# FPGABank1X.net
KiCad netlist of a schematic drawn in Altium Designer
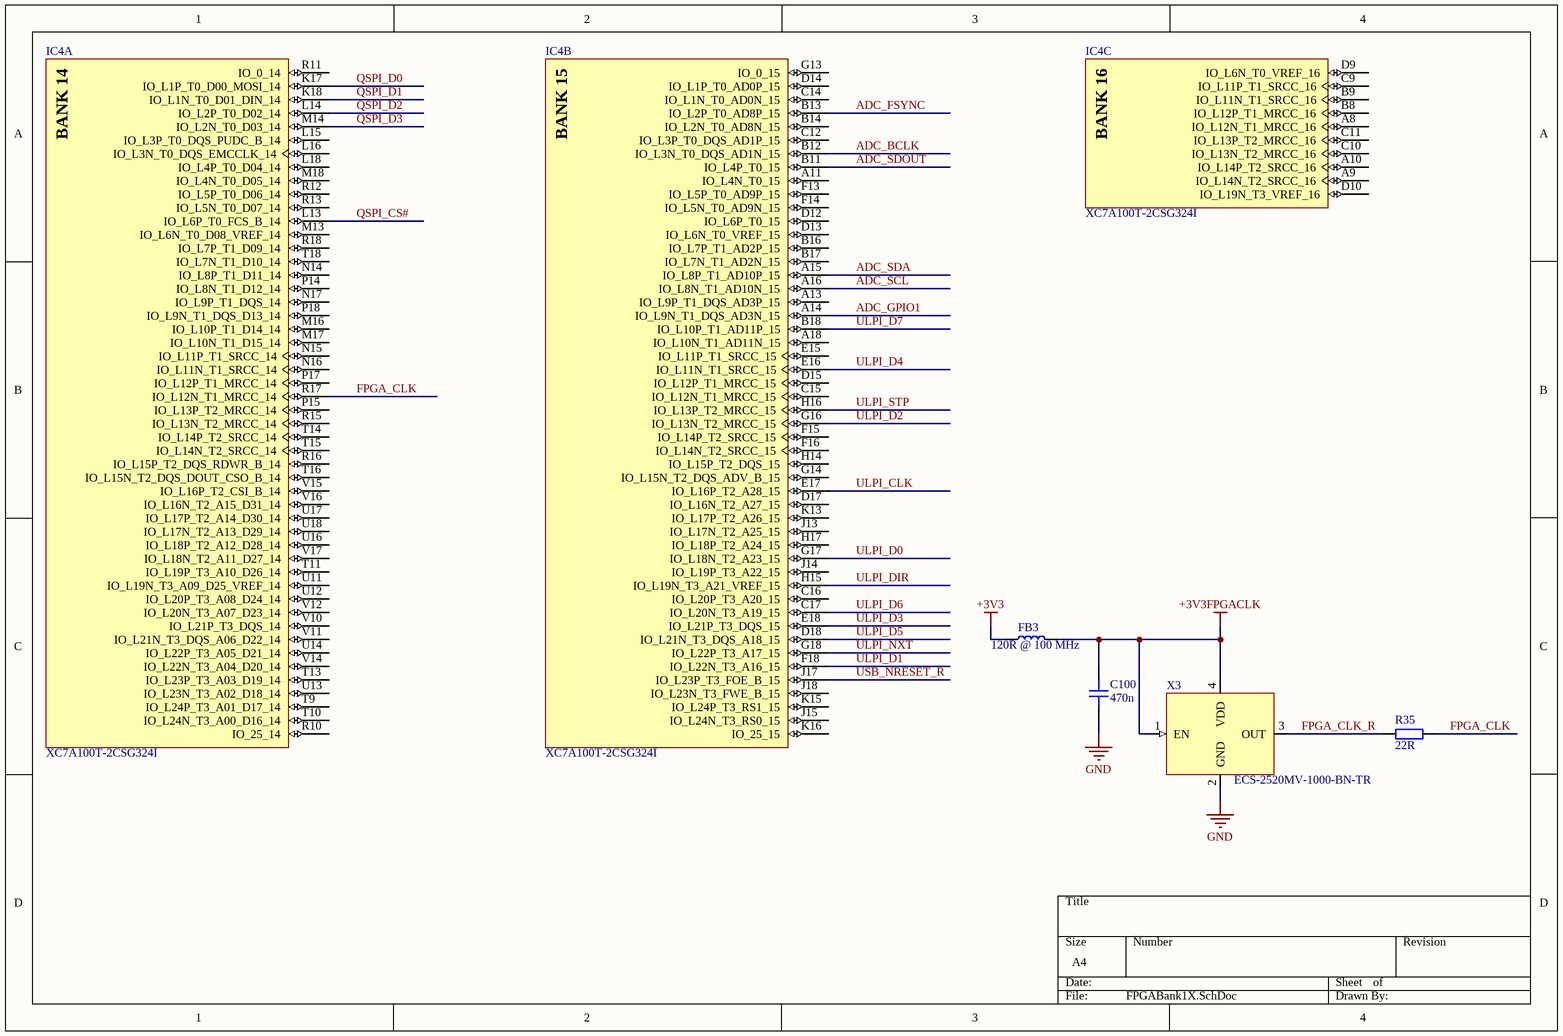
[diagram p0: FPGABank1X.SchDoc]

(export (version "E")
  (design (tool "Eeschema 10.0.6"))
  (components
    (comp (ref "C100")
      (value "470n")
      (footprint "CAP_0201")
      (description "Capacitor SMD 0201")
      (libsource (lib "Schematic-Lib-PhilsLab") (part "CAP_0201"))
    )
    (comp (ref "FB3")
      (value "120R @ 100 MHz")
      (footprint "Footprint-Lib-PhilsLab:IND_0201")
      (description "Inductor SMD 0201")
      (fields
        (field (name "MANUFACTURER_PART_NUMBER") "LQP03HQ56NH02D")
        (field (name "MOUSER PART NUMBER") "81-LQP03HQ56NH02D")
      )
      (libsource (lib "Schematic-Lib-PhilsLab") (part "IND_0201"))
    )
    (comp (ref "IC4")
      (value "XC7A100T-2CSG324I")
      (footprint "CSG324")
      (description "Artix-7 FPGA, 210 User I/Os, 0 GTP, 324-Ball BGA, Speed Grade 2, Industrial Grade, Pb-Free")
      (fields (field (name "GENERIC PART NUMBER") "XC7A100T") (field (name "MANUFACTURER") "Xilinx"))
      (libsource (lib "Schematic-Lib-PhilsLab") (part "XC7A100T-2CSG324I"))
    )
    (comp (ref "R35")
      (value "22R")
      (footprint "RES_0201")
      (description "Resistor SMD 0201")
      (libsource (lib "Schematic-Lib-PhilsLab") (part "RES_0201"))
    )
    (comp (ref "X3")
      (value "ECS-2520MV-1000-BN-TR")
      (footprint "XTAL_2520")
      (fields
        (field (name "MANUFACTURER") "ECS")
        (field (name "MANUFACTURER PART NUMBER") "ECS-2520MV-130-BN-TR")
      )
      (libsource (lib "Schematic-Lib-PhilsLab") (part "ECS-2520MV-130-BN-TR"))
    )
  )
  (nets
    (net (code "1") (name "+3V3") (class "Default")
      (node (ref "FB3") (pin "1") (pinfunction "1_1") (pintype "passive"))
    )
    (net (code "2") (name "+3V3FPGACLK") (class "Default")
      (node (ref "C100") (pin "2") (pinfunction "2_2") (pintype "passive"))
      (node (ref "FB3") (pin "2") (pinfunction "2_2") (pintype "passive"))
      (node (ref "X3") (pin "1") (pinfunction "EN_1") (pintype "input"))
      (node (ref "X3") (pin "4") (pinfunction "VDD_4") (pintype "power_in"))
    )
    (net (code "3") (name "/ADC_BCLK") (class "Default")
      (node (ref "IC4") (pin "B12") (pinfunction "IO_L3N_T0_DQS_AD1N_15_B12") (pintype "bidirectional"))
    )
    (net (code "4") (name "/ADC_FSYNC") (class "Default")
      (node (ref "IC4") (pin "B13") (pinfunction "IO_L2P_T0_AD8P_15_B13") (pintype "bidirectional"))
    )
    (net (code "5") (name "/ADC_GPIO1") (class "Default")
      (node (ref "IC4") (pin "A14") (pinfunction "IO_L9N_T1_DQS_AD3N_15_A14") (pintype "bidirectional"))
    )
    (net (code "6") (name "/ADC_SCL") (class "Default")
      (node (ref "IC4") (pin "A16") (pinfunction "IO_L8N_T1_AD10N_15_A16") (pintype "bidirectional"))
    )
    (net (code "7") (name "/ADC_SDA") (class "Default")
      (node (ref "IC4") (pin "A15") (pinfunction "IO_L8P_T1_AD10P_15_A15") (pintype "bidirectional"))
    )
    (net (code "8") (name "/ADC_SDOUT") (class "Default")
      (node (ref "IC4") (pin "B11") (pinfunction "IO_L4P_T0_15_B11") (pintype "bidirectional"))
    )
    (net (code "9") (name "/FPGA_CLK") (class "Default")
      (node (ref "IC4") (pin "R17") (pinfunction "IO_L12N_T1_MRCC_14_R17") (pintype "bidirectional"))
      (node (ref "R35") (pin "2") (pinfunction "2_2") (pintype "passive"))
    )
    (net (code "10") (name "/FPGA_CLK_R") (class "Default")
      (node (ref "R35") (pin "1") (pinfunction "1_1") (pintype "passive"))
      (node (ref "X3") (pin "3") (pinfunction "OUT_3") (pintype "passive"))
    )
    (net (code "11") (name "/QSPI_CS#") (class "Default")
      (node (ref "IC4") (pin "L13") (pinfunction "IO_L6P_T0_FCS_B_14_L13") (pintype "bidirectional"))
    )
    (net (code "12") (name "/QSPI_D0") (class "Default")
      (node (ref "IC4") (pin "K17") (pinfunction "IO_L1P_T0_D00_MOSI_14_K17") (pintype "bidirectional"))
    )
    (net (code "13") (name "/QSPI_D1") (class "Default")
      (node (ref "IC4") (pin "K18") (pinfunction "IO_L1N_T0_D01_DIN_14_K18") (pintype "bidirectional"))
    )
    (net (code "14") (name "/QSPI_D2") (class "Default")
      (node (ref "IC4") (pin "L14") (pinfunction "IO_L2P_T0_D02_14_L14") (pintype "bidirectional"))
    )
    (net (code "15") (name "/QSPI_D3") (class "Default")
      (node (ref "IC4") (pin "M14") (pinfunction "IO_L2N_T0_D03_14_M14") (pintype "bidirectional"))
    )
    (net (code "16") (name "/ULPI_CLK") (class "Default")
      (node (ref "IC4") (pin "E17") (pinfunction "IO_L16P_T2_A28_15_E17") (pintype "bidirectional"))
    )
    (net (code "17") (name "/ULPI_D0") (class "Default")
      (node (ref "IC4") (pin "G17") (pinfunction "IO_L18N_T2_A23_15_G17") (pintype "bidirectional"))
    )
    (net (code "18") (name "/ULPI_D1") (class "Default")
      (node (ref "IC4") (pin "F18") (pinfunction "IO_L22N_T3_A16_15_F18") (pintype "bidirectional"))
    )
    (net (code "19") (name "/ULPI_D2") (class "Default")
      (node (ref "IC4") (pin "G16") (pinfunction "IO_L13N_T2_MRCC_15_G16") (pintype "bidirectional"))
    )
    (net (code "20") (name "/ULPI_D3") (class "Default")
      (node (ref "IC4") (pin "E18") (pinfunction "IO_L21P_T3_DQS_15_E18") (pintype "bidirectional"))
    )
    (net (code "21") (name "/ULPI_D4") (class "Default")
      (node (ref "IC4") (pin "E16") (pinfunction "IO_L11N_T1_SRCC_15_E16") (pintype "bidirectional"))
    )
    (net (code "22") (name "/ULPI_D5") (class "Default")
      (node (ref "IC4") (pin "D18") (pinfunction "IO_L21N_T3_DQS_A18_15_D18") (pintype "bidirectional"))
    )
    (net (code "23") (name "/ULPI_D6") (class "Default")
      (node (ref "IC4") (pin "C17") (pinfunction "IO_L20N_T3_A19_15_C17") (pintype "bidirectional"))
    )
    (net (code "24") (name "/ULPI_D7") (class "Default")
      (node (ref "IC4") (pin "B18") (pinfunction "IO_L10P_T1_AD11P_15_B18") (pintype "bidirectional"))
    )
    (net (code "25") (name "/ULPI_DIR") (class "Default")
      (node (ref "IC4") (pin "H15") (pinfunction "IO_L19N_T3_A21_VREF_15_H15") (pintype "bidirectional"))
    )
    (net (code "26") (name "/ULPI_NXT") (class "Default")
      (node (ref "IC4") (pin "G18") (pinfunction "IO_L22P_T3_A17_15_G18") (pintype "bidirectional"))
    )
    (net (code "27") (name "/ULPI_STP") (class "Default")
      (node (ref "IC4") (pin "H16") (pinfunction "IO_L13P_T2_MRCC_15_H16") (pintype "bidirectional"))
    )
    (net (code "28") (name "/USB_NRESET_R") (class "Default")
      (node (ref "IC4") (pin "J17") (pinfunction "IO_L23P_T3_FOE_B_15_J17") (pintype "bidirectional"))
    )
    (net (code "29") (name "GND") (class "Default")
      (node (ref "C100") (pin "1") (pinfunction "1_1") (pintype "passive"))
      (node (ref "X3") (pin "2") (pinfunction "GND_2") (pintype "power_in"))
    )
    (net (code "30") (name "unconnected-(IC4A-IO_0_14-PadR11)") (class "Default")
      (node (ref "IC4") (pin "R11") (pinfunction "IO_0_14_R11") (pintype "bidirectional"))
    )
    (net (code "31") (name "unconnected-(IC4A-IO_25_14-PadR10)") (class "Default")
      (node (ref "IC4") (pin "R10") (pinfunction "IO_25_14_R10") (pintype "bidirectional"))
    )
    (net (code "32") (name "unconnected-(IC4A-IO_L3N_T0_DQS_EMCCLK_14-PadL16)") (class "Default")
      (node (ref "IC4") (pin "L16") (pinfunction "IO_L3N_T0_DQS_EMCCLK_14_L16") (pintype "bidirectional"))
    )
    (net (code "33") (name "unconnected-(IC4A-IO_L3P_T0_DQS_PUDC_B_14-PadL15)") (class "Default")
      (node (ref "IC4") (pin "L15") (pinfunction "IO_L3P_T0_DQS_PUDC_B_14_L15") (pintype "bidirectional"))
    )
    (net (code "34") (name "unconnected-(IC4A-IO_L4N_T0_D05_14-PadM18)") (class "Default")
      (node (ref "IC4") (pin "M18") (pinfunction "IO_L4N_T0_D05_14_M18") (pintype "bidirectional"))
    )
    (net (code "35") (name "unconnected-(IC4A-IO_L4P_T0_D04_14-PadL18)") (class "Default")
      (node (ref "IC4") (pin "L18") (pinfunction "IO_L4P_T0_D04_14_L18") (pintype "bidirectional"))
    )
    (net (code "36") (name "unconnected-(IC4A-IO_L5N_T0_D07_14-PadR13)") (class "Default")
      (node (ref "IC4") (pin "R13") (pinfunction "IO_L5N_T0_D07_14_R13") (pintype "bidirectional"))
    )
    (net (code "37") (name "unconnected-(IC4A-IO_L5P_T0_D06_14-PadR12)") (class "Default")
      (node (ref "IC4") (pin "R12") (pinfunction "IO_L5P_T0_D06_14_R12") (pintype "bidirectional"))
    )
    (net (code "38") (name "unconnected-(IC4A-IO_L6N_T0_D08_VREF_14-PadM13)") (class "Default")
      (node (ref "IC4") (pin "M13") (pinfunction "IO_L6N_T0_D08_VREF_14_M13") (pintype "bidirectional"))
    )
    (net (code "39") (name "unconnected-(IC4A-IO_L7N_T1_D10_14-PadT18)") (class "Default")
      (node (ref "IC4") (pin "T18") (pinfunction "IO_L7N_T1_D10_14_T18") (pintype "bidirectional"))
    )
    (net (code "40") (name "unconnected-(IC4A-IO_L7P_T1_D09_14-PadR18)") (class "Default")
      (node (ref "IC4") (pin "R18") (pinfunction "IO_L7P_T1_D09_14_R18") (pintype "bidirectional"))
    )
    (net (code "41") (name "unconnected-(IC4A-IO_L8N_T1_D12_14-PadP14)") (class "Default")
      (node (ref "IC4") (pin "P14") (pinfunction "IO_L8N_T1_D12_14_P14") (pintype "bidirectional"))
    )
    (net (code "42") (name "unconnected-(IC4A-IO_L8P_T1_D11_14-PadN14)") (class "Default")
      (node (ref "IC4") (pin "N14") (pinfunction "IO_L8P_T1_D11_14_N14") (pintype "bidirectional"))
    )
    (net (code "43") (name "unconnected-(IC4A-IO_L9N_T1_DQS_D13_14-PadP18)") (class "Default")
      (node (ref "IC4") (pin "P18") (pinfunction "IO_L9N_T1_DQS_D13_14_P18") (pintype "bidirectional"))
    )
    (net (code "44") (name "unconnected-(IC4A-IO_L9P_T1_DQS_14-PadN17)") (class "Default")
      (node (ref "IC4") (pin "N17") (pinfunction "IO_L9P_T1_DQS_14_N17") (pintype "bidirectional"))
    )
    (net (code "45") (name "unconnected-(IC4A-IO_L10N_T1_D15_14-PadM17)") (class "Default")
      (node (ref "IC4") (pin "M17") (pinfunction "IO_L10N_T1_D15_14_M17") (pintype "bidirectional"))
    )
    (net (code "46") (name "unconnected-(IC4A-IO_L10P_T1_D14_14-PadM16)") (class "Default")
      (node (ref "IC4") (pin "M16") (pinfunction "IO_L10P_T1_D14_14_M16") (pintype "bidirectional"))
    )
    (net (code "47") (name "unconnected-(IC4A-IO_L11N_T1_SRCC_14-PadN16)") (class "Default")
      (node (ref "IC4") (pin "N16") (pinfunction "IO_L11N_T1_SRCC_14_N16") (pintype "bidirectional"))
    )
    (net (code "48") (name "unconnected-(IC4A-IO_L11P_T1_SRCC_14-PadN15)") (class "Default")
      (node (ref "IC4") (pin "N15") (pinfunction "IO_L11P_T1_SRCC_14_N15") (pintype "bidirectional"))
    )
    (net (code "49") (name "unconnected-(IC4A-IO_L12P_T1_MRCC_14-PadP17)") (class "Default")
      (node (ref "IC4") (pin "P17") (pinfunction "IO_L12P_T1_MRCC_14_P17") (pintype "bidirectional"))
    )
    (net (code "50") (name "unconnected-(IC4A-IO_L13N_T2_MRCC_14-PadR15)") (class "Default")
      (node (ref "IC4") (pin "R15") (pinfunction "IO_L13N_T2_MRCC_14_R15") (pintype "bidirectional"))
    )
    (net (code "51") (name "unconnected-(IC4A-IO_L13P_T2_MRCC_14-PadP15)") (class "Default")
      (node (ref "IC4") (pin "P15") (pinfunction "IO_L13P_T2_MRCC_14_P15") (pintype "bidirectional"))
    )
    (net (code "52") (name "unconnected-(IC4A-IO_L14N_T2_SRCC_14-PadT15)") (class "Default")
      (node (ref "IC4") (pin "T15") (pinfunction "IO_L14N_T2_SRCC_14_T15") (pintype "bidirectional"))
    )
    (net (code "53") (name "unconnected-(IC4A-IO_L14P_T2_SRCC_14-PadT14)") (class "Default")
      (node (ref "IC4") (pin "T14") (pinfunction "IO_L14P_T2_SRCC_14_T14") (pintype "bidirectional"))
    )
    (net (code "54") (name "unconnected-(IC4A-IO_L15N_T2_DQS_DOUT_CSO_B_14-PadT16)") (class "Default")
      (node (ref "IC4") (pin "T16") (pinfunction "IO_L15N_T2_DQS_DOUT_CSO_B_14_T16") (pintype "bidirectional"))
    )
    (net (code "55") (name "unconnected-(IC4A-IO_L15P_T2_DQS_RDWR_B_14-PadR16)") (class "Default")
      (node (ref "IC4") (pin "R16") (pinfunction "IO_L15P_T2_DQS_RDWR_B_14_R16") (pintype "bidirectional"))
    )
    (net (code "56") (name "unconnected-(IC4A-IO_L16N_T2_A15_D31_14-PadV16)") (class "Default")
      (node (ref "IC4") (pin "V16") (pinfunction "IO_L16N_T2_A15_D31_14_V16") (pintype "bidirectional"))
    )
    (net (code "57") (name "unconnected-(IC4A-IO_L16P_T2_CSI_B_14-PadV15)") (class "Default")
      (node (ref "IC4") (pin "V15") (pinfunction "IO_L16P_T2_CSI_B_14_V15") (pintype "bidirectional"))
    )
    (net (code "58") (name "unconnected-(IC4A-IO_L17N_T2_A13_D29_14-PadU18)") (class "Default")
      (node (ref "IC4") (pin "U18") (pinfunction "IO_L17N_T2_A13_D29_14_U18") (pintype "bidirectional"))
    )
    (net (code "59") (name "unconnected-(IC4A-IO_L17P_T2_A14_D30_14-PadU17)") (class "Default")
      (node (ref "IC4") (pin "U17") (pinfunction "IO_L17P_T2_A14_D30_14_U17") (pintype "bidirectional"))
    )
    (net (code "60") (name "unconnected-(IC4A-IO_L18N_T2_A11_D27_14-PadV17)") (class "Default")
      (node (ref "IC4") (pin "V17") (pinfunction "IO_L18N_T2_A11_D27_14_V17") (pintype "bidirectional"))
    )
    (net (code "61") (name "unconnected-(IC4A-IO_L18P_T2_A12_D28_14-PadU16)") (class "Default")
      (node (ref "IC4") (pin "U16") (pinfunction "IO_L18P_T2_A12_D28_14_U16") (pintype "bidirectional"))
    )
    (net (code "62") (name "unconnected-(IC4A-IO_L19N_T3_A09_D25_VREF_14-PadU11)") (class "Default")
      (node (ref "IC4") (pin "U11") (pinfunction "IO_L19N_T3_A09_D25_VREF_14_U11") (pintype "bidirectional"))
    )
    (net (code "63") (name "unconnected-(IC4A-IO_L19P_T3_A10_D26_14-PadT11)") (class "Default")
      (node (ref "IC4") (pin "T11") (pinfunction "IO_L19P_T3_A10_D26_14_T11") (pintype "bidirectional"))
    )
    (net (code "64") (name "unconnected-(IC4A-IO_L20N_T3_A07_D23_14-PadV12)") (class "Default")
      (node (ref "IC4") (pin "V12") (pinfunction "IO_L20N_T3_A07_D23_14_V12") (pintype "bidirectional"))
    )
    (net (code "65") (name "unconnected-(IC4A-IO_L20P_T3_A08_D24_14-PadU12)") (class "Default")
      (node (ref "IC4") (pin "U12") (pinfunction "IO_L20P_T3_A08_D24_14_U12") (pintype "bidirectional"))
    )
    (net (code "66") (name "unconnected-(IC4A-IO_L21N_T3_DQS_A06_D22_14-PadV11)") (class "Default")
      (node (ref "IC4") (pin "V11") (pinfunction "IO_L21N_T3_DQS_A06_D22_14_V11") (pintype "bidirectional"))
    )
    (net (code "67") (name "unconnected-(IC4A-IO_L21P_T3_DQS_14-PadV10)") (class "Default")
      (node (ref "IC4") (pin "V10") (pinfunction "IO_L21P_T3_DQS_14_V10") (pintype "bidirectional"))
    )
    (net (code "68") (name "unconnected-(IC4A-IO_L22N_T3_A04_D20_14-PadV14)") (class "Default")
      (node (ref "IC4") (pin "V14") (pinfunction "IO_L22N_T3_A04_D20_14_V14") (pintype "bidirectional"))
    )
    (net (code "69") (name "unconnected-(IC4A-IO_L22P_T3_A05_D21_14-PadU14)") (class "Default")
      (node (ref "IC4") (pin "U14") (pinfunction "IO_L22P_T3_A05_D21_14_U14") (pintype "bidirectional"))
    )
    (net (code "70") (name "unconnected-(IC4A-IO_L23N_T3_A02_D18_14-PadU13)") (class "Default")
      (node (ref "IC4") (pin "U13") (pinfunction "IO_L23N_T3_A02_D18_14_U13") (pintype "bidirectional"))
    )
    (net (code "71") (name "unconnected-(IC4A-IO_L23P_T3_A03_D19_14-PadT13)") (class "Default")
      (node (ref "IC4") (pin "T13") (pinfunction "IO_L23P_T3_A03_D19_14_T13") (pintype "bidirectional"))
    )
    (net (code "72") (name "unconnected-(IC4A-IO_L24N_T3_A00_D16_14-PadT10)") (class "Default")
      (node (ref "IC4") (pin "T10") (pinfunction "IO_L24N_T3_A00_D16_14_T10") (pintype "bidirectional"))
    )
    (net (code "73") (name "unconnected-(IC4A-IO_L24P_T3_A01_D17_14-PadT9)") (class "Default")
      (node (ref "IC4") (pin "T9") (pinfunction "IO_L24P_T3_A01_D17_14_T9") (pintype "bidirectional"))
    )
    (net (code "74") (name "unconnected-(IC4B-IO_0_15-PadG13)") (class "Default")
      (node (ref "IC4") (pin "G13") (pinfunction "IO_0_15_G13") (pintype "bidirectional"))
    )
    (net (code "75") (name "unconnected-(IC4B-IO_25_15-PadK16)") (class "Default")
      (node (ref "IC4") (pin "K16") (pinfunction "IO_25_15_K16") (pintype "bidirectional"))
    )
    (net (code "76") (name "unconnected-(IC4B-IO_L1N_T0_AD0N_15-PadC14)") (class "Default")
      (node (ref "IC4") (pin "C14") (pinfunction "IO_L1N_T0_AD0N_15_C14") (pintype "bidirectional"))
    )
    (net (code "77") (name "unconnected-(IC4B-IO_L1P_T0_AD0P_15-PadD14)") (class "Default")
      (node (ref "IC4") (pin "D14") (pinfunction "IO_L1P_T0_AD0P_15_D14") (pintype "bidirectional"))
    )
    (net (code "78") (name "unconnected-(IC4B-IO_L2N_T0_AD8N_15-PadB14)") (class "Default")
      (node (ref "IC4") (pin "B14") (pinfunction "IO_L2N_T0_AD8N_15_B14") (pintype "bidirectional"))
    )
    (net (code "79") (name "unconnected-(IC4B-IO_L3P_T0_DQS_AD1P_15-PadC12)") (class "Default")
      (node (ref "IC4") (pin "C12") (pinfunction "IO_L3P_T0_DQS_AD1P_15_C12") (pintype "bidirectional"))
    )
    (net (code "80") (name "unconnected-(IC4B-IO_L4N_T0_15-PadA11)") (class "Default")
      (node (ref "IC4") (pin "A11") (pinfunction "IO_L4N_T0_15_A11") (pintype "bidirectional"))
    )
    (net (code "81") (name "unconnected-(IC4B-IO_L5N_T0_AD9N_15-PadF14)") (class "Default")
      (node (ref "IC4") (pin "F14") (pinfunction "IO_L5N_T0_AD9N_15_F14") (pintype "bidirectional"))
    )
    (net (code "82") (name "unconnected-(IC4B-IO_L5P_T0_AD9P_15-PadF13)") (class "Default")
      (node (ref "IC4") (pin "F13") (pinfunction "IO_L5P_T0_AD9P_15_F13") (pintype "bidirectional"))
    )
    (net (code "83") (name "unconnected-(IC4B-IO_L6N_T0_VREF_15-PadD13)") (class "Default")
      (node (ref "IC4") (pin "D13") (pinfunction "IO_L6N_T0_VREF_15_D13") (pintype "bidirectional"))
    )
    (net (code "84") (name "unconnected-(IC4B-IO_L6P_T0_15-PadD12)") (class "Default")
      (node (ref "IC4") (pin "D12") (pinfunction "IO_L6P_T0_15_D12") (pintype "bidirectional"))
    )
    (net (code "85") (name "unconnected-(IC4B-IO_L7N_T1_AD2N_15-PadB17)") (class "Default")
      (node (ref "IC4") (pin "B17") (pinfunction "IO_L7N_T1_AD2N_15_B17") (pintype "bidirectional"))
    )
    (net (code "86") (name "unconnected-(IC4B-IO_L7P_T1_AD2P_15-PadB16)") (class "Default")
      (node (ref "IC4") (pin "B16") (pinfunction "IO_L7P_T1_AD2P_15_B16") (pintype "bidirectional"))
    )
    (net (code "87") (name "unconnected-(IC4B-IO_L9P_T1_DQS_AD3P_15-PadA13)") (class "Default")
      (node (ref "IC4") (pin "A13") (pinfunction "IO_L9P_T1_DQS_AD3P_15_A13") (pintype "bidirectional"))
    )
    (net (code "88") (name "unconnected-(IC4B-IO_L10N_T1_AD11N_15-PadA18)") (class "Default")
      (node (ref "IC4") (pin "A18") (pinfunction "IO_L10N_T1_AD11N_15_A18") (pintype "bidirectional"))
    )
    (net (code "89") (name "unconnected-(IC4B-IO_L11P_T1_SRCC_15-PadE15)") (class "Default")
      (node (ref "IC4") (pin "E15") (pinfunction "IO_L11P_T1_SRCC_15_E15") (pintype "bidirectional"))
    )
    (net (code "90") (name "unconnected-(IC4B-IO_L12N_T1_MRCC_15-PadC15)") (class "Default")
      (node (ref "IC4") (pin "C15") (pinfunction "IO_L12N_T1_MRCC_15_C15") (pintype "bidirectional"))
    )
    (net (code "91") (name "unconnected-(IC4B-IO_L12P_T1_MRCC_15-PadD15)") (class "Default")
      (node (ref "IC4") (pin "D15") (pinfunction "IO_L12P_T1_MRCC_15_D15") (pintype "bidirectional"))
    )
    (net (code "92") (name "unconnected-(IC4B-IO_L14N_T2_SRCC_15-PadF16)") (class "Default")
      (node (ref "IC4") (pin "F16") (pinfunction "IO_L14N_T2_SRCC_15_F16") (pintype "bidirectional"))
    )
    (net (code "93") (name "unconnected-(IC4B-IO_L14P_T2_SRCC_15-PadF15)") (class "Default")
      (node (ref "IC4") (pin "F15") (pinfunction "IO_L14P_T2_SRCC_15_F15") (pintype "bidirectional"))
    )
    (net (code "94") (name "unconnected-(IC4B-IO_L15N_T2_DQS_ADV_B_15-PadG14)") (class "Default")
      (node (ref "IC4") (pin "G14") (pinfunction "IO_L15N_T2_DQS_ADV_B_15_G14") (pintype "bidirectional"))
    )
    (net (code "95") (name "unconnected-(IC4B-IO_L15P_T2_DQS_15-PadH14)") (class "Default")
      (node (ref "IC4") (pin "H14") (pinfunction "IO_L15P_T2_DQS_15_H14") (pintype "bidirectional"))
    )
    (net (code "96") (name "unconnected-(IC4B-IO_L16N_T2_A27_15-PadD17)") (class "Default")
      (node (ref "IC4") (pin "D17") (pinfunction "IO_L16N_T2_A27_15_D17") (pintype "bidirectional"))
    )
    (net (code "97") (name "unconnected-(IC4B-IO_L17N_T2_A25_15-PadJ13)") (class "Default")
      (node (ref "IC4") (pin "J13") (pinfunction "IO_L17N_T2_A25_15_J13") (pintype "bidirectional"))
    )
    (net (code "98") (name "unconnected-(IC4B-IO_L17P_T2_A26_15-PadK13)") (class "Default")
      (node (ref "IC4") (pin "K13") (pinfunction "IO_L17P_T2_A26_15_K13") (pintype "bidirectional"))
    )
    (net (code "99") (name "unconnected-(IC4B-IO_L18P_T2_A24_15-PadH17)") (class "Default")
      (node (ref "IC4") (pin "H17") (pinfunction "IO_L18P_T2_A24_15_H17") (pintype "bidirectional"))
    )
    (net (code "100") (name "unconnected-(IC4B-IO_L19P_T3_A22_15-PadJ14)") (class "Default")
      (node (ref "IC4") (pin "J14") (pinfunction "IO_L19P_T3_A22_15_J14") (pintype "bidirectional"))
    )
    (net (code "101") (name "unconnected-(IC4B-IO_L20P_T3_A20_15-PadC16)") (class "Default")
      (node (ref "IC4") (pin "C16") (pinfunction "IO_L20P_T3_A20_15_C16") (pintype "bidirectional"))
    )
    (net (code "102") (name "unconnected-(IC4B-IO_L23N_T3_FWE_B_15-PadJ18)") (class "Default")
      (node (ref "IC4") (pin "J18") (pinfunction "IO_L23N_T3_FWE_B_15_J18") (pintype "bidirectional"))
    )
    (net (code "103") (name "unconnected-(IC4B-IO_L24N_T3_RS0_15-PadJ15)") (class "Default")
      (node (ref "IC4") (pin "J15") (pinfunction "IO_L24N_T3_RS0_15_J15") (pintype "bidirectional"))
    )
    (net (code "104") (name "unconnected-(IC4B-IO_L24P_T3_RS1_15-PadK15)") (class "Default")
      (node (ref "IC4") (pin "K15") (pinfunction "IO_L24P_T3_RS1_15_K15") (pintype "bidirectional"))
    )
    (net (code "105") (name "unconnected-(IC4C-IO_L6N_T0_VREF_16-PadD9)") (class "Default")
      (node (ref "IC4") (pin "D9") (pinfunction "IO_L6N_T0_VREF_16_D9") (pintype "bidirectional"))
    )
    (net (code "106") (name "unconnected-(IC4C-IO_L11N_T1_SRCC_16-PadB9)") (class "Default")
      (node (ref "IC4") (pin "B9") (pinfunction "IO_L11N_T1_SRCC_16_B9") (pintype "bidirectional"))
    )
    (net (code "107") (name "unconnected-(IC4C-IO_L11P_T1_SRCC_16-PadC9)") (class "Default")
      (node (ref "IC4") (pin "C9") (pinfunction "IO_L11P_T1_SRCC_16_C9") (pintype "bidirectional"))
    )
    (net (code "108") (name "unconnected-(IC4C-IO_L12N_T1_MRCC_16-PadA8)") (class "Default")
      (node (ref "IC4") (pin "A8") (pinfunction "IO_L12N_T1_MRCC_16_A8") (pintype "bidirectional"))
    )
    (net (code "109") (name "unconnected-(IC4C-IO_L12P_T1_MRCC_16-PadB8)") (class "Default")
      (node (ref "IC4") (pin "B8") (pinfunction "IO_L12P_T1_MRCC_16_B8") (pintype "bidirectional"))
    )
    (net (code "110") (name "unconnected-(IC4C-IO_L13N_T2_MRCC_16-PadC10)") (class "Default")
      (node (ref "IC4") (pin "C10") (pinfunction "IO_L13N_T2_MRCC_16_C10") (pintype "bidirectional"))
    )
    (net (code "111") (name "unconnected-(IC4C-IO_L13P_T2_MRCC_16-PadC11)") (class "Default")
      (node (ref "IC4") (pin "C11") (pinfunction "IO_L13P_T2_MRCC_16_C11") (pintype "bidirectional"))
    )
    (net (code "112") (name "unconnected-(IC4C-IO_L14N_T2_SRCC_16-PadA9)") (class "Default")
      (node (ref "IC4") (pin "A9") (pinfunction "IO_L14N_T2_SRCC_16_A9") (pintype "bidirectional"))
    )
    (net (code "113") (name "unconnected-(IC4C-IO_L14P_T2_SRCC_16-PadA10)") (class "Default")
      (node (ref "IC4") (pin "A10") (pinfunction "IO_L14P_T2_SRCC_16_A10") (pintype "bidirectional"))
    )
    (net (code "114") (name "unconnected-(IC4C-IO_L19N_T3_VREF_16-PadD10)") (class "Default")
      (node (ref "IC4") (pin "D10") (pinfunction "IO_L19N_T3_VREF_16_D10") (pintype "bidirectional"))
    )
  )
)
